# pj8.net
KiCad netlist of a schematic drawn in EAGLE
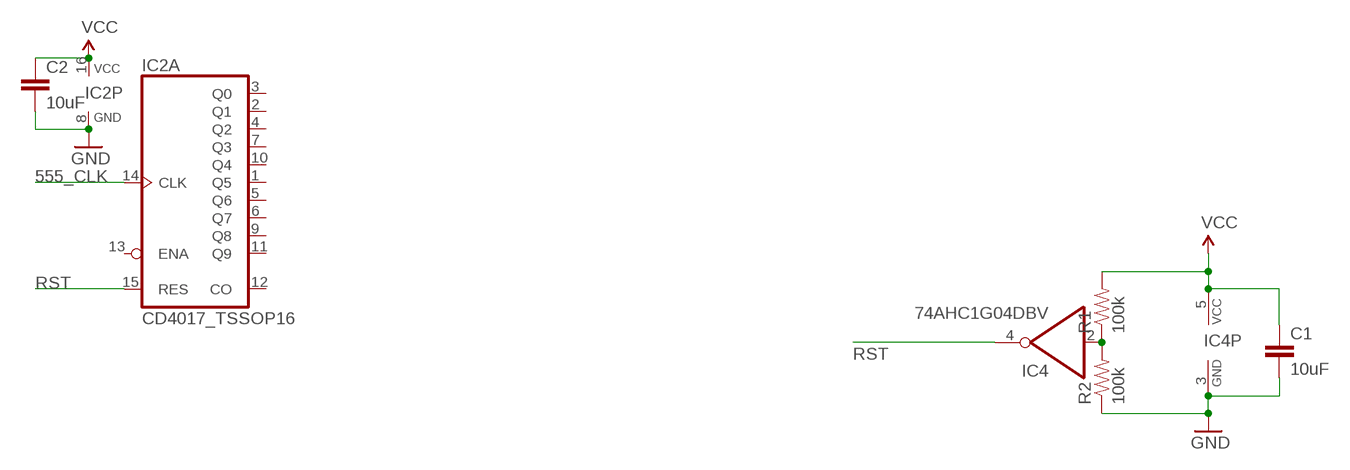
[diagram p0: schematic, sheet 1]

(export (version "E")
  (design (tool "Eeschema 10.0.6"))
  (components
    (comp (ref "C1")
      (value "10uF")
      (footprint "eagle-import:0603-CAP")
      (libsource (lib "eagle-import") (part "10UF-6.3V-20%(0603)"))
    )
    (comp (ref "C2")
      (value "10uF")
      (footprint "eagle-import:0603-CAP")
      (libsource (lib "eagle-import") (part "10UF-6.3V-20%(0603)"))
    )
    (comp (ref "IC2")
      (value "CD4017_TSSOP16")
      (footprint "eagle-import:TSSOP16")
      (libsource (lib "eagle-import") (part "CD4017_TSSOP16"))
    )
    (comp (ref "IC4")
      (value "74AHC1G04DBV")
      (footprint "eagle-import:SOT23-5")
      (libsource (lib "eagle-import") (part "741G04DBVAHC"))
    )
    (comp (ref "R1")
      (value "100k")
      (footprint "eagle-import:0603-RES")
      (libsource (lib "eagle-import") (part "100KOHM-1/10W-1%(0603)"))
    )
    (comp (ref "R2")
      (value "100k")
      (footprint "eagle-import:0603-RES")
      (libsource (lib "eagle-import") (part "100KOHM-1/10W-1%(0603)"))
    )
  )
  (nets
    (net (code "1") (name "/555_CLK") (class "Default")
      (node (ref "IC2") (pin "14") (pinfunction "CLK_14") (pintype "input"))
    )
    (net (code "2") (name "/RST") (class "Default")
      (node (ref "IC2") (pin "15") (pinfunction "RES_15") (pintype "input"))
      (node (ref "IC4") (pin "4") (pinfunction "O_4") (pintype "output"))
    )
    (net (code "3") (name "GND") (class "Default")
      (node (ref "C1") (pin "2") (pinfunction "2_2") (pintype "passive"))
      (node (ref "C2") (pin "2") (pinfunction "2_2") (pintype "passive"))
      (node (ref "IC2") (pin "8") (pinfunction "GND_8") (pintype "power_in"))
      (node (ref "IC4") (pin "3") (pinfunction "GND_3") (pintype "power_in"))
      (node (ref "R2") (pin "1") (pinfunction "1_1") (pintype "passive"))
    )
    (net (code "4") (name "Net-(IC4A-I)") (class "Default")
      (node (ref "IC4") (pin "2") (pinfunction "I_2") (pintype "input"))
      (node (ref "R1") (pin "1") (pinfunction "1_1") (pintype "passive"))
      (node (ref "R2") (pin "2") (pinfunction "2_2") (pintype "passive"))
    )
    (net (code "5") (name "VCC") (class "Default")
      (node (ref "C1") (pin "1") (pinfunction "1_1") (pintype "passive"))
      (node (ref "C2") (pin "1") (pinfunction "1_1") (pintype "passive"))
      (node (ref "IC2") (pin "16") (pinfunction "VCC_16") (pintype "power_in"))
      (node (ref "IC4") (pin "5") (pinfunction "VCC_5") (pintype "power_in"))
      (node (ref "R1") (pin "2") (pinfunction "2_2") (pintype "passive"))
    )
    (net (code "6") (name "unconnected-(IC2A-CO-Pad12)") (class "Default")
      (node (ref "IC2") (pin "12") (pinfunction "CO_12") (pintype "output"))
    )
    (net (code "7") (name "unconnected-(IC2A-ENA-Pad13)") (class "Default")
      (node (ref "IC2") (pin "13") (pinfunction "ENA_13") (pintype "input"))
    )
    (net (code "8") (name "unconnected-(IC2A-Q0-Pad3)") (class "Default")
      (node (ref "IC2") (pin "3") (pinfunction "Q0_3") (pintype "output"))
    )
    (net (code "9") (name "unconnected-(IC2A-Q1-Pad2)") (class "Default")
      (node (ref "IC2") (pin "2") (pinfunction "Q1_2") (pintype "output"))
    )
    (net (code "10") (name "unconnected-(IC2A-Q2-Pad4)") (class "Default")
      (node (ref "IC2") (pin "4") (pinfunction "Q2_4") (pintype "output"))
    )
    (net (code "11") (name "unconnected-(IC2A-Q3-Pad7)") (class "Default")
      (node (ref "IC2") (pin "7") (pinfunction "Q3_7") (pintype "output"))
    )
    (net (code "12") (name "unconnected-(IC2A-Q4-Pad10)") (class "Default")
      (node (ref "IC2") (pin "10") (pinfunction "Q4_10") (pintype "output"))
    )
    (net (code "13") (name "unconnected-(IC2A-Q5-Pad1)") (class "Default")
      (node (ref "IC2") (pin "1") (pinfunction "Q5_1") (pintype "output"))
    )
    (net (code "14") (name "unconnected-(IC2A-Q6-Pad5)") (class "Default")
      (node (ref "IC2") (pin "5") (pinfunction "Q6_5") (pintype "output"))
    )
    (net (code "15") (name "unconnected-(IC2A-Q7-Pad6)") (class "Default")
      (node (ref "IC2") (pin "6") (pinfunction "Q7_6") (pintype "output"))
    )
    (net (code "16") (name "unconnected-(IC2A-Q8-Pad9)") (class "Default")
      (node (ref "IC2") (pin "9") (pinfunction "Q8_9") (pintype "output"))
    )
    (net (code "17") (name "unconnected-(IC2A-Q9-Pad11)") (class "Default")
      (node (ref "IC2") (pin "11") (pinfunction "Q9_11") (pintype "output"))
    )
  )
)
